# BLM_2017.net
KiCad netlist of a schematic drawn in Altium Designer
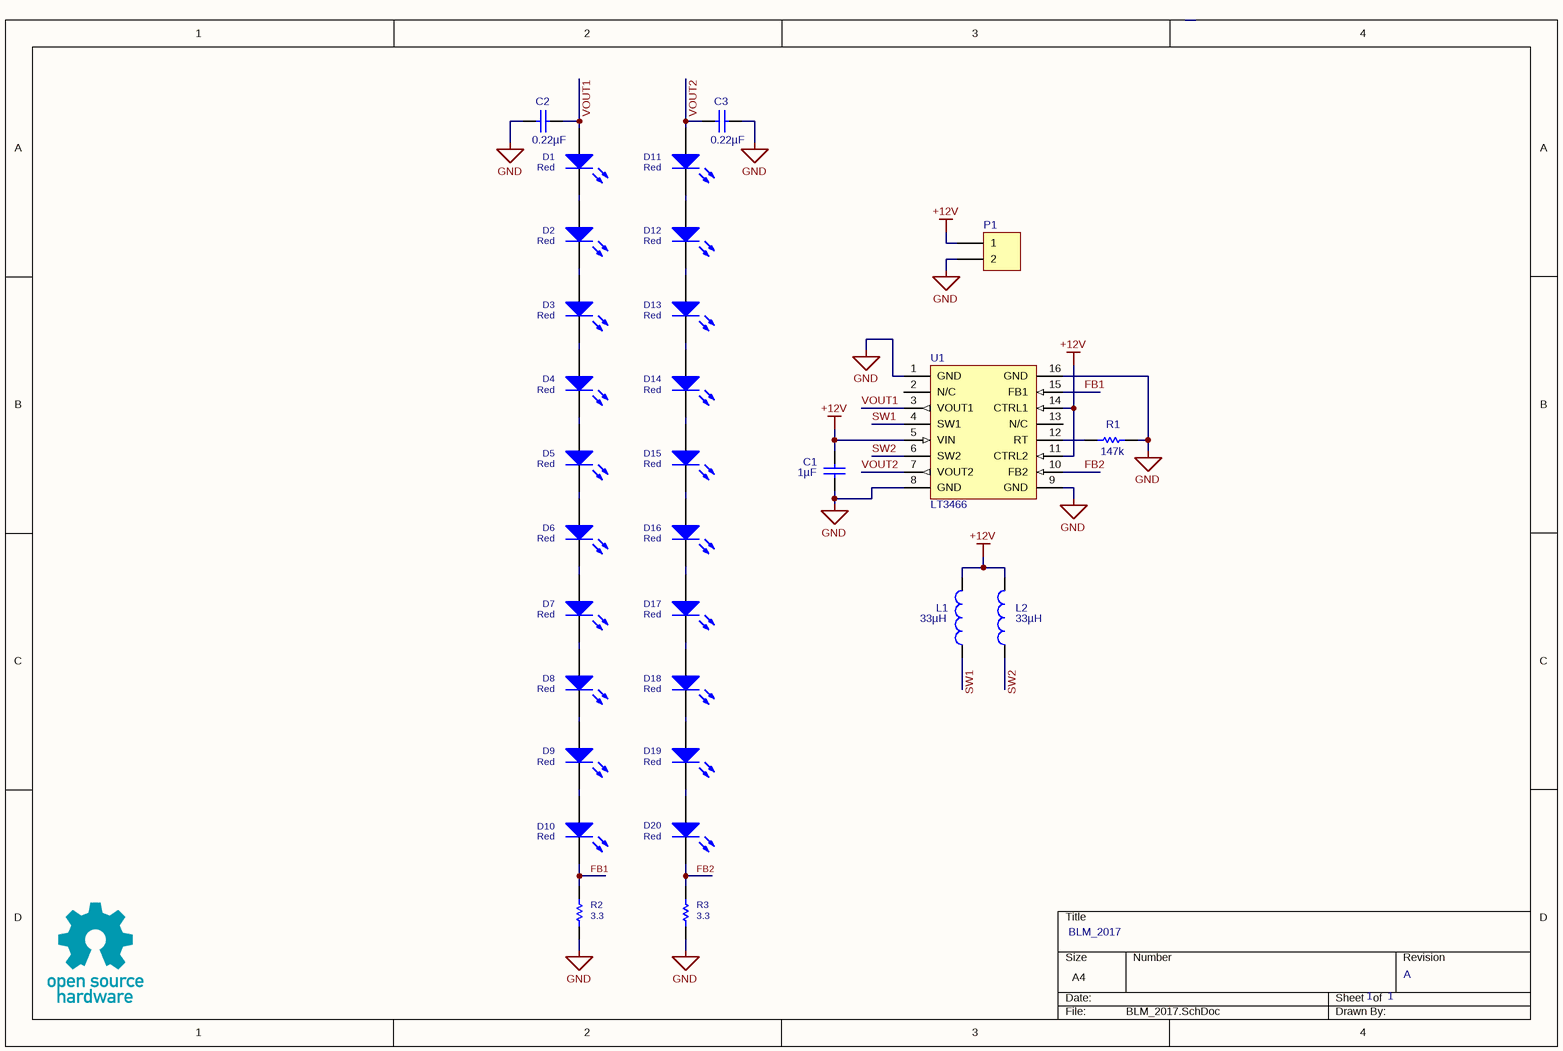
[diagram p0: BLM_2017.SchDoc]

(export (version "E")
  (design (tool "Eeschema 10.0.6"))
  (components
    (comp (ref "C1")
      (value "1µF")
      (footprint "TDK C-Series (2012)")
      (description "Capacitor (Semiconductor SIM Model)")
      (fields (field (name "Comment") "Cap Semi") (field (name "PUBLISHER") "Altium Limited"))
      (libsource (lib "Miscellaneous Devices") (part "Cap Semi"))
    )
    (comp (ref "C2")
      (value "0.22µF")
      (footprint "TDK C-Series (1608)")
      (description "Capacitor (Semiconductor SIM Model)")
      (fields (field (name "Comment") "Cap Semi") (field (name "PUBLISHER") "Altium Limited"))
      (libsource (lib "Miscellaneous Devices") (part "Cap Semi"))
    )
    (comp (ref "C3")
      (value "0.22µF")
      (footprint "TDK C-Series (1608)")
      (description "Capacitor (Semiconductor SIM Model)")
      (fields (field (name "Comment") "Cap Semi") (field (name "PUBLISHER") "Altium Limited"))
      (libsource (lib "Miscellaneous Devices") (part "Cap Semi"))
    )
    (comp (ref "D1")
      (value "Red")
      (footprint "OPTEK OVS5MxBCR4-Series (2-SMD)")
      (description "Typical INFRARED GaAs LED")
      (fields (field (name "PUBLISHER") "Altium Limited"))
      (libsource (lib "Miscellaneous Devices") (part "LED0"))
    )
    (comp (ref "D2")
      (value "Red")
      (footprint "OPTEK OVS5MxBCR4-Series (2-SMD)")
      (description "Typical INFRARED GaAs LED")
      (fields (field (name "PUBLISHER") "Altium Limited"))
      (libsource (lib "Miscellaneous Devices") (part "LED0"))
    )
    (comp (ref "D3")
      (value "Red")
      (footprint "OPTEK OVS5MxBCR4-Series (2-SMD)")
      (description "Typical INFRARED GaAs LED")
      (fields (field (name "PUBLISHER") "Altium Limited"))
      (libsource (lib "Miscellaneous Devices") (part "LED0"))
    )
    (comp (ref "D4")
      (value "Red")
      (footprint "OPTEK OVS5MxBCR4-Series (2-SMD)")
      (description "Typical INFRARED GaAs LED")
      (fields (field (name "PUBLISHER") "Altium Limited"))
      (libsource (lib "Miscellaneous Devices") (part "LED0"))
    )
    (comp (ref "D5")
      (value "Red")
      (footprint "OPTEK OVS5MxBCR4-Series (2-SMD)")
      (description "Typical INFRARED GaAs LED")
      (fields (field (name "PUBLISHER") "Altium Limited"))
      (libsource (lib "Miscellaneous Devices") (part "LED0"))
    )
    (comp (ref "D6")
      (value "Red")
      (footprint "OPTEK OVS5MxBCR4-Series (2-SMD)")
      (description "Typical INFRARED GaAs LED")
      (fields (field (name "PUBLISHER") "Altium Limited"))
      (libsource (lib "Miscellaneous Devices") (part "LED0"))
    )
    (comp (ref "D7")
      (value "Red")
      (footprint "OPTEK OVS5MxBCR4-Series (2-SMD)")
      (description "Typical INFRARED GaAs LED")
      (fields (field (name "PUBLISHER") "Altium Limited"))
      (libsource (lib "Miscellaneous Devices") (part "LED0"))
    )
    (comp (ref "D8")
      (value "Red")
      (footprint "OPTEK OVS5MxBCR4-Series (2-SMD)")
      (description "Typical INFRARED GaAs LED")
      (fields (field (name "PUBLISHER") "Altium Limited"))
      (libsource (lib "Miscellaneous Devices") (part "LED0"))
    )
    (comp (ref "D9")
      (value "Red")
      (footprint "OPTEK OVS5MxBCR4-Series (2-SMD)")
      (description "Typical INFRARED GaAs LED")
      (fields (field (name "PUBLISHER") "Altium Limited"))
      (libsource (lib "Miscellaneous Devices") (part "LED0"))
    )
    (comp (ref "D10")
      (value "Red")
      (footprint "OPTEK OVS5MxBCR4-Series (2-SMD)")
      (description "Typical INFRARED GaAs LED")
      (fields (field (name "PUBLISHER") "Altium Limited"))
      (libsource (lib "Miscellaneous Devices") (part "LED0"))
    )
    (comp (ref "D11")
      (value "Red")
      (footprint "OPTEK OVS5MxBCR4-Series (2-SMD)")
      (description "Typical INFRARED GaAs LED")
      (fields (field (name "PUBLISHER") "Altium Limited"))
      (libsource (lib "Miscellaneous Devices") (part "LED0"))
    )
    (comp (ref "D12")
      (value "Red")
      (footprint "OPTEK OVS5MxBCR4-Series (2-SMD)")
      (description "Typical INFRARED GaAs LED")
      (fields (field (name "PUBLISHER") "Altium Limited"))
      (libsource (lib "Miscellaneous Devices") (part "LED0"))
    )
    (comp (ref "D13")
      (value "Red")
      (footprint "OPTEK OVS5MxBCR4-Series (2-SMD)")
      (description "Typical INFRARED GaAs LED")
      (fields (field (name "PUBLISHER") "Altium Limited"))
      (libsource (lib "Miscellaneous Devices") (part "LED0"))
    )
    (comp (ref "D14")
      (value "Red")
      (footprint "OPTEK OVS5MxBCR4-Series (2-SMD)")
      (description "Typical INFRARED GaAs LED")
      (fields (field (name "PUBLISHER") "Altium Limited"))
      (libsource (lib "Miscellaneous Devices") (part "LED0"))
    )
    (comp (ref "D15")
      (value "Red")
      (footprint "OPTEK OVS5MxBCR4-Series (2-SMD)")
      (description "Typical INFRARED GaAs LED")
      (fields (field (name "PUBLISHER") "Altium Limited"))
      (libsource (lib "Miscellaneous Devices") (part "LED0"))
    )
    (comp (ref "D16")
      (value "Red")
      (footprint "OPTEK OVS5MxBCR4-Series (2-SMD)")
      (description "Typical INFRARED GaAs LED")
      (fields (field (name "PUBLISHER") "Altium Limited"))
      (libsource (lib "Miscellaneous Devices") (part "LED0"))
    )
    (comp (ref "D17")
      (value "Red")
      (footprint "OPTEK OVS5MxBCR4-Series (2-SMD)")
      (description "Typical INFRARED GaAs LED")
      (fields (field (name "PUBLISHER") "Altium Limited"))
      (libsource (lib "Miscellaneous Devices") (part "LED0"))
    )
    (comp (ref "D18")
      (value "Red")
      (footprint "OPTEK OVS5MxBCR4-Series (2-SMD)")
      (description "Typical INFRARED GaAs LED")
      (fields (field (name "PUBLISHER") "Altium Limited"))
      (libsource (lib "Miscellaneous Devices") (part "LED0"))
    )
    (comp (ref "D19")
      (value "Red")
      (footprint "OPTEK OVS5MxBCR4-Series (2-SMD)")
      (description "Typical INFRARED GaAs LED")
      (fields (field (name "PUBLISHER") "Altium Limited"))
      (libsource (lib "Miscellaneous Devices") (part "LED0"))
    )
    (comp (ref "D20")
      (value "Red")
      (footprint "OPTEK OVS5MxBCR4-Series (2-SMD)")
      (description "Typical INFRARED GaAs LED")
      (fields (field (name "PUBLISHER") "Altium Limited"))
      (libsource (lib "Miscellaneous Devices") (part "LED0"))
    )
    (comp (ref "L1")
      (value "33µH")
      (footprint "Bourns SRN4018-Series")
      (description "Inductor")
      (fields (field (name "PUBLISHER") "Altium Limited"))
      (libsource (lib "Miscellaneous Devices") (part "Inductor"))
    )
    (comp (ref "L2")
      (value "33µH")
      (footprint "Bourns SRN4018-Series")
      (description "Inductor")
      (fields (field (name "PUBLISHER") "Altium Limited"))
      (libsource (lib "Miscellaneous Devices") (part "Inductor"))
    )
    (comp (ref "P1")
      (value "2-Pin Bare Wire Pads")
      (footprint "2-Pin Bare Wire Pads")
      (libsource (lib "BLM_2017") (part "2-Pin Bare Wire Pads"))
    )
    (comp (ref "R1")
      (value "147k")
      (footprint "Panasonic ERJ-Series (1608)")
      (description "Resistor")
      (fields (field (name "Comment") "Res1") (field (name "PUBLISHER") "Altium Limited"))
      (libsource (lib "Miscellaneous Devices") (part "Res1"))
    )
    (comp (ref "R2")
      (value "3.3")
      (footprint "Panasonic ERJ-Series (1608)")
      (description "Resistor")
      (fields (field (name "Comment") "Res1") (field (name "PUBLISHER") "Altium Limited"))
      (libsource (lib "Miscellaneous Devices") (part "Res1"))
    )
    (comp (ref "R3")
      (value "3.3")
      (footprint "Panasonic ERJ-Series (1608)")
      (description "Resistor")
      (fields (field (name "Comment") "Res1") (field (name "PUBLISHER") "Altium Limited"))
      (libsource (lib "Miscellaneous Devices") (part "Res1"))
    )
    (comp (ref "U1")
      (value "LT3466")
      (footprint "Linear Technology LT3466 (16-TSSOP)")
      (description "2-Channel Step-Up LED Driver")
      (libsource (lib "TSAL_2017") (part "Linear Technology LT3466"))
    )
  )
  (nets
    (net (code "1") (name "+12V") (class "Default")
      (node (ref "C1") (pin "2") (pinfunction "2_2") (pintype "passive"))
      (node (ref "L1") (pin "2") (pinfunction "2_2") (pintype "passive"))
      (node (ref "L2") (pin "2") (pinfunction "2_2") (pintype "passive"))
      (node (ref "P1") (pin "1") (pinfunction "1_1") (pintype "passive"))
      (node (ref "U1") (pin "11") (pinfunction "CTRL2_11") (pintype "input"))
      (node (ref "U1") (pin "14") (pinfunction "CTRL1_14") (pintype "input"))
      (node (ref "U1") (pin "5") (pinfunction "VIN_5") (pintype "input"))
    )
    (net (code "2") (name "/FB1") (class "Default")
      (node (ref "D10") (pin "2") (pinfunction "K_2") (pintype "passive"))
      (node (ref "R2") (pin "2") (pinfunction "2_2") (pintype "passive"))
      (node (ref "U1") (pin "15") (pinfunction "FB1_15") (pintype "input"))
    )
    (net (code "3") (name "/FB2") (class "Default")
      (node (ref "D20") (pin "2") (pinfunction "K_2") (pintype "passive"))
      (node (ref "R3") (pin "2") (pinfunction "2_2") (pintype "passive"))
      (node (ref "U1") (pin "10") (pinfunction "FB2_10") (pintype "input"))
    )
    (net (code "4") (name "/SW1") (class "Default")
      (node (ref "L1") (pin "1") (pinfunction "1_1") (pintype "passive"))
      (node (ref "U1") (pin "4") (pinfunction "SW1_4") (pintype "passive"))
    )
    (net (code "5") (name "/SW2") (class "Default")
      (node (ref "L2") (pin "1") (pinfunction "1_1") (pintype "passive"))
      (node (ref "U1") (pin "6") (pinfunction "SW2_6") (pintype "passive"))
    )
    (net (code "6") (name "/VOUT1") (class "Default")
      (node (ref "C2") (pin "1") (pinfunction "1_1") (pintype "passive"))
      (node (ref "D1") (pin "1") (pinfunction "A_1") (pintype "passive"))
      (node (ref "U1") (pin "3") (pinfunction "VOUT1_3") (pintype "output"))
    )
    (net (code "7") (name "/VOUT2") (class "Default")
      (node (ref "C3") (pin "2") (pinfunction "2_2") (pintype "passive"))
      (node (ref "D11") (pin "1") (pinfunction "A_1") (pintype "passive"))
      (node (ref "U1") (pin "7") (pinfunction "VOUT2_7") (pintype "output"))
    )
    (net (code "8") (name "GND") (class "Default")
      (node (ref "C1") (pin "1") (pinfunction "1_1") (pintype "passive"))
      (node (ref "C2") (pin "2") (pinfunction "2_2") (pintype "passive"))
      (node (ref "C3") (pin "1") (pinfunction "1_1") (pintype "passive"))
      (node (ref "P1") (pin "2") (pinfunction "2_2") (pintype "passive"))
      (node (ref "R1") (pin "1") (pinfunction "1_1") (pintype "passive"))
      (node (ref "R2") (pin "1") (pinfunction "1_1") (pintype "passive"))
      (node (ref "R3") (pin "1") (pinfunction "1_1") (pintype "passive"))
      (node (ref "U1") (pin "1") (pinfunction "GND_1") (pintype "power_in"))
      (node (ref "U1") (pin "16") (pinfunction "GND_16") (pintype "power_in"))
      (node (ref "U1") (pin "8") (pinfunction "GND_8") (pintype "power_in"))
      (node (ref "U1") (pin "9") (pinfunction "GND_9") (pintype "power_in"))
    )
    (net (code "9") (name "Net-(D1-K)") (class "Default")
      (node (ref "D1") (pin "2") (pinfunction "K_2") (pintype "passive"))
      (node (ref "D2") (pin "1") (pinfunction "A_1") (pintype "passive"))
    )
    (net (code "10") (name "Net-(D2-K)") (class "Default")
      (node (ref "D2") (pin "2") (pinfunction "K_2") (pintype "passive"))
      (node (ref "D3") (pin "1") (pinfunction "A_1") (pintype "passive"))
    )
    (net (code "11") (name "Net-(D3-K)") (class "Default")
      (node (ref "D3") (pin "2") (pinfunction "K_2") (pintype "passive"))
      (node (ref "D4") (pin "1") (pinfunction "A_1") (pintype "passive"))
    )
    (net (code "12") (name "Net-(D4-K)") (class "Default")
      (node (ref "D4") (pin "2") (pinfunction "K_2") (pintype "passive"))
      (node (ref "D5") (pin "1") (pinfunction "A_1") (pintype "passive"))
    )
    (net (code "13") (name "Net-(D5-K)") (class "Default")
      (node (ref "D5") (pin "2") (pinfunction "K_2") (pintype "passive"))
      (node (ref "D6") (pin "1") (pinfunction "A_1") (pintype "passive"))
    )
    (net (code "14") (name "Net-(D6-K)") (class "Default")
      (node (ref "D6") (pin "2") (pinfunction "K_2") (pintype "passive"))
      (node (ref "D7") (pin "1") (pinfunction "A_1") (pintype "passive"))
    )
    (net (code "15") (name "Net-(D7-K)") (class "Default")
      (node (ref "D7") (pin "2") (pinfunction "K_2") (pintype "passive"))
      (node (ref "D8") (pin "1") (pinfunction "A_1") (pintype "passive"))
    )
    (net (code "16") (name "Net-(D8-K)") (class "Default")
      (node (ref "D8") (pin "2") (pinfunction "K_2") (pintype "passive"))
      (node (ref "D9") (pin "1") (pinfunction "A_1") (pintype "passive"))
    )
    (net (code "17") (name "Net-(D10-A)") (class "Default")
      (node (ref "D10") (pin "1") (pinfunction "A_1") (pintype "passive"))
      (node (ref "D9") (pin "2") (pinfunction "K_2") (pintype "passive"))
    )
    (net (code "18") (name "Net-(D11-K)") (class "Default")
      (node (ref "D11") (pin "2") (pinfunction "K_2") (pintype "passive"))
      (node (ref "D12") (pin "1") (pinfunction "A_1") (pintype "passive"))
    )
    (net (code "19") (name "Net-(D12-K)") (class "Default")
      (node (ref "D12") (pin "2") (pinfunction "K_2") (pintype "passive"))
      (node (ref "D13") (pin "1") (pinfunction "A_1") (pintype "passive"))
    )
    (net (code "20") (name "Net-(D13-K)") (class "Default")
      (node (ref "D13") (pin "2") (pinfunction "K_2") (pintype "passive"))
      (node (ref "D14") (pin "1") (pinfunction "A_1") (pintype "passive"))
    )
    (net (code "21") (name "Net-(D14-K)") (class "Default")
      (node (ref "D14") (pin "2") (pinfunction "K_2") (pintype "passive"))
      (node (ref "D15") (pin "1") (pinfunction "A_1") (pintype "passive"))
    )
    (net (code "22") (name "Net-(D15-K)") (class "Default")
      (node (ref "D15") (pin "2") (pinfunction "K_2") (pintype "passive"))
      (node (ref "D16") (pin "1") (pinfunction "A_1") (pintype "passive"))
    )
    (net (code "23") (name "Net-(D16-K)") (class "Default")
      (node (ref "D16") (pin "2") (pinfunction "K_2") (pintype "passive"))
      (node (ref "D17") (pin "1") (pinfunction "A_1") (pintype "passive"))
    )
    (net (code "24") (name "Net-(D17-K)") (class "Default")
      (node (ref "D17") (pin "2") (pinfunction "K_2") (pintype "passive"))
      (node (ref "D18") (pin "1") (pinfunction "A_1") (pintype "passive"))
    )
    (net (code "25") (name "Net-(D18-K)") (class "Default")
      (node (ref "D18") (pin "2") (pinfunction "K_2") (pintype "passive"))
      (node (ref "D19") (pin "1") (pinfunction "A_1") (pintype "passive"))
    )
    (net (code "26") (name "Net-(D19-K)") (class "Default")
      (node (ref "D19") (pin "2") (pinfunction "K_2") (pintype "passive"))
      (node (ref "D20") (pin "1") (pinfunction "A_1") (pintype "passive"))
    )
    (net (code "27") (name "Net-(U1-RT)") (class "Default")
      (node (ref "R1") (pin "2") (pinfunction "2_2") (pintype "passive"))
      (node (ref "U1") (pin "12") (pinfunction "RT_12") (pintype "passive"))
    )
    (net (code "28") (name "unconnected-(U1-N{slash}C-Pad2)") (class "Default")
      (node (ref "U1") (pin "2") (pinfunction "N/C_2") (pintype "passive"))
    )
    (net (code "29") (name "unconnected-(U1-N{slash}C-Pad13)") (class "Default")
      (node (ref "U1") (pin "13") (pinfunction "N/C_13") (pintype "passive"))
    )
  )
)
